# BoardB-FPGA2.net
KiCad netlist of a schematic drawn in Altium Designer
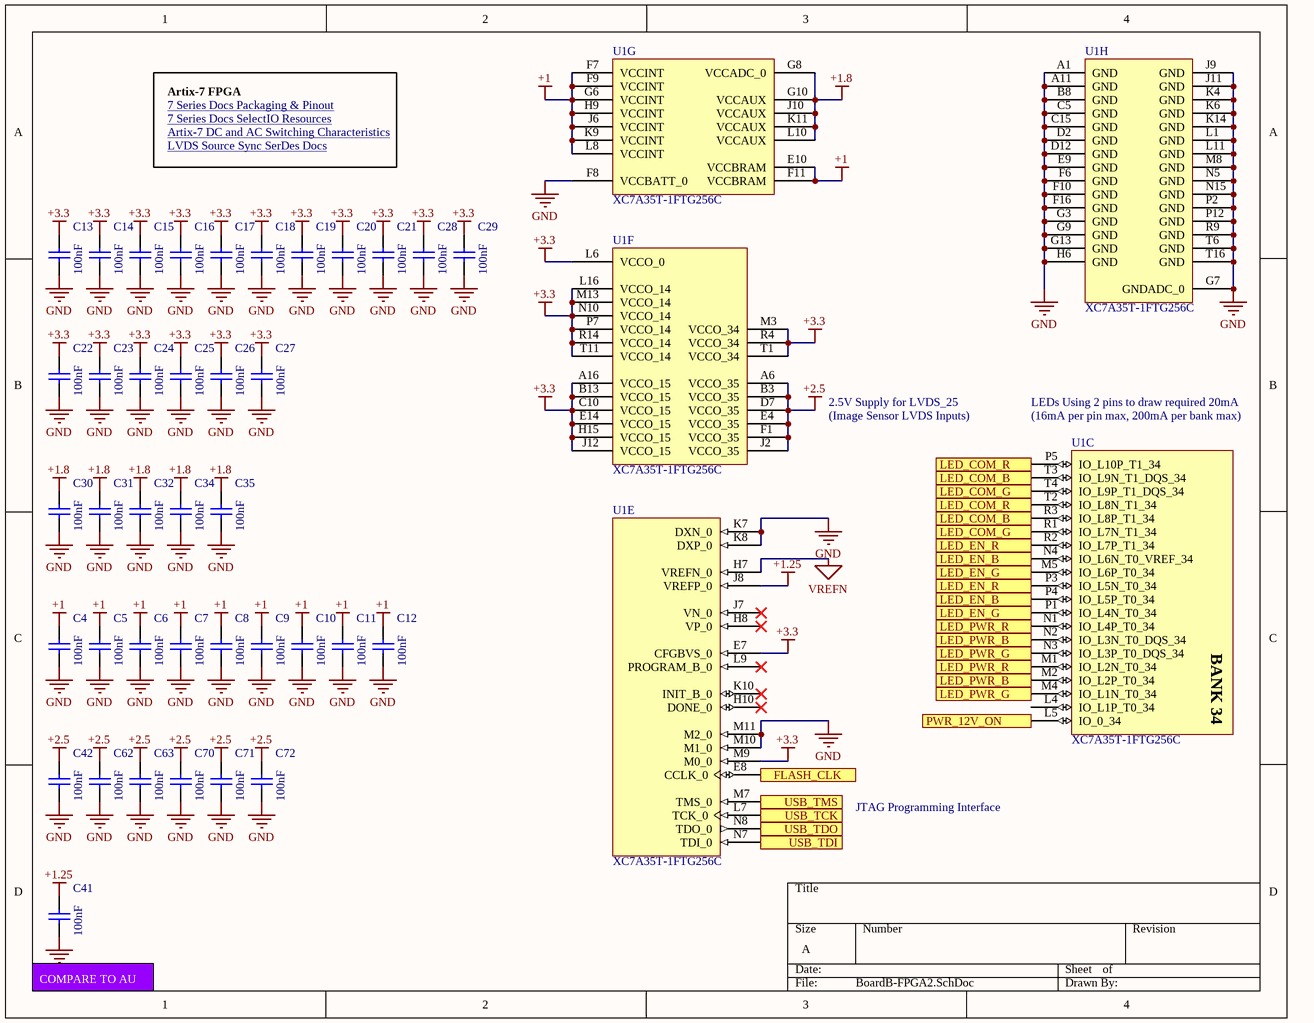
[diagram p0: BoardB-FPGA2.SchDoc]

(export (version "E")
  (design (tool "Eeschema 10.0.6"))
  (components
    (comp (ref "C4")
      (value "100nF")
      (footprint "CAPC0603X33X15ML03T05")
      (fields (field (name "MANUFACTURER") "Samsung") (field (name "PART NUMBER") "CL03A104KQ3NNNC"))
      (libsource (lib "Altium Content Vault") (part "CAP"))
    )
    (comp (ref "C5")
      (value "100nF")
      (footprint "CAPC0603X33X15ML03T05")
      (fields (field (name "MANUFACTURER") "Samsung") (field (name "PART NUMBER") "CL03A104KQ3NNNC"))
      (libsource (lib "Altium Content Vault") (part "CAP"))
    )
    (comp (ref "C6")
      (value "100nF")
      (footprint "CAPC0603X33X15ML03T05")
      (fields (field (name "MANUFACTURER") "Samsung") (field (name "PART NUMBER") "CL03A104KQ3NNNC"))
      (libsource (lib "Altium Content Vault") (part "CAP"))
    )
    (comp (ref "C7")
      (value "100nF")
      (footprint "CAPC0603X33X15ML03T05")
      (fields (field (name "MANUFACTURER") "Samsung") (field (name "PART NUMBER") "CL03A104KQ3NNNC"))
      (libsource (lib "Altium Content Vault") (part "CAP"))
    )
    (comp (ref "C8")
      (value "100nF")
      (footprint "CAPC0603X33X15ML03T05")
      (fields (field (name "MANUFACTURER") "Samsung") (field (name "PART NUMBER") "CL03A104KQ3NNNC"))
      (libsource (lib "Altium Content Vault") (part "CAP"))
    )
    (comp (ref "C9")
      (value "100nF")
      (footprint "CAPC0603X33X15ML03T05")
      (fields (field (name "MANUFACTURER") "Samsung") (field (name "PART NUMBER") "CL03A104KQ3NNNC"))
      (libsource (lib "Altium Content Vault") (part "CAP"))
    )
    (comp (ref "C10")
      (value "100nF")
      (footprint "CAPC0603X33X15ML03T05")
      (fields (field (name "MANUFACTURER") "Samsung") (field (name "PART NUMBER") "CL03A104KQ3NNNC"))
      (libsource (lib "Altium Content Vault") (part "CAP"))
    )
    (comp (ref "C11")
      (value "100nF")
      (footprint "CAPC0603X33X15ML03T05")
      (fields (field (name "MANUFACTURER") "Samsung") (field (name "PART NUMBER") "CL03A104KQ3NNNC"))
      (libsource (lib "Altium Content Vault") (part "CAP"))
    )
    (comp (ref "C12")
      (value "100nF")
      (footprint "CAPC0603X33X15ML03T05")
      (fields (field (name "MANUFACTURER") "Samsung") (field (name "PART NUMBER") "CL03A104KQ3NNNC"))
      (libsource (lib "Altium Content Vault") (part "CAP"))
    )
    (comp (ref "C13")
      (value "100nF")
      (footprint "CAPC0603X33X15ML03T05")
      (fields (field (name "MANUFACTURER") "Samsung") (field (name "PART NUMBER") "CL03A104KQ3NNNC"))
      (libsource (lib "Altium Content Vault") (part "CAP"))
    )
    (comp (ref "C14")
      (value "100nF")
      (footprint "CAPC0603X33X15ML03T05")
      (fields (field (name "MANUFACTURER") "Samsung") (field (name "PART NUMBER") "CL03A104KQ3NNNC"))
      (libsource (lib "Altium Content Vault") (part "CAP"))
    )
    (comp (ref "C15")
      (value "100nF")
      (footprint "CAPC0603X33X15ML03T05")
      (fields (field (name "MANUFACTURER") "Samsung") (field (name "PART NUMBER") "CL03A104KQ3NNNC"))
      (libsource (lib "Altium Content Vault") (part "CAP"))
    )
    (comp (ref "C16")
      (value "100nF")
      (footprint "CAPC0603X33X15ML03T05")
      (fields (field (name "MANUFACTURER") "Samsung") (field (name "PART NUMBER") "CL03A104KQ3NNNC"))
      (libsource (lib "Altium Content Vault") (part "CAP"))
    )
    (comp (ref "C17")
      (value "100nF")
      (footprint "CAPC0603X33X15ML03T05")
      (fields (field (name "MANUFACTURER") "Samsung") (field (name "PART NUMBER") "CL03A104KQ3NNNC"))
      (libsource (lib "Altium Content Vault") (part "CAP"))
    )
    (comp (ref "C18")
      (value "100nF")
      (footprint "CAPC0603X33X15ML03T05")
      (fields (field (name "MANUFACTURER") "Samsung") (field (name "PART NUMBER") "CL03A104KQ3NNNC"))
      (libsource (lib "Altium Content Vault") (part "CAP"))
    )
    (comp (ref "C19")
      (value "100nF")
      (footprint "CAPC0603X33X15ML03T05")
      (fields (field (name "MANUFACTURER") "Samsung") (field (name "PART NUMBER") "CL03A104KQ3NNNC"))
      (libsource (lib "Altium Content Vault") (part "CAP"))
    )
    (comp (ref "C20")
      (value "100nF")
      (footprint "CAPC0603X33X15ML03T05")
      (fields (field (name "MANUFACTURER") "Samsung") (field (name "PART NUMBER") "CL03A104KQ3NNNC"))
      (libsource (lib "Altium Content Vault") (part "CAP"))
    )
    (comp (ref "C21")
      (value "100nF")
      (footprint "CAPC0603X33X15ML03T05")
      (fields (field (name "MANUFACTURER") "Samsung") (field (name "PART NUMBER") "CL03A104KQ3NNNC"))
      (libsource (lib "Altium Content Vault") (part "CAP"))
    )
    (comp (ref "C22")
      (value "100nF")
      (footprint "CAPC0603X33X15ML03T05")
      (fields (field (name "MANUFACTURER") "Samsung") (field (name "PART NUMBER") "CL03A104KQ3NNNC"))
      (libsource (lib "Altium Content Vault") (part "CAP"))
    )
    (comp (ref "C23")
      (value "100nF")
      (footprint "CAPC0603X33X15ML03T05")
      (fields (field (name "MANUFACTURER") "Samsung") (field (name "PART NUMBER") "CL03A104KQ3NNNC"))
      (libsource (lib "Altium Content Vault") (part "CAP"))
    )
    (comp (ref "C24")
      (value "100nF")
      (footprint "CAPC0603X33X15ML03T05")
      (fields (field (name "MANUFACTURER") "Samsung") (field (name "PART NUMBER") "CL03A104KQ3NNNC"))
      (libsource (lib "Altium Content Vault") (part "CAP"))
    )
    (comp (ref "C25")
      (value "100nF")
      (footprint "CAPC0603X33X15ML03T05")
      (fields (field (name "MANUFACTURER") "Samsung") (field (name "PART NUMBER") "CL03A104KQ3NNNC"))
      (libsource (lib "Altium Content Vault") (part "CAP"))
    )
    (comp (ref "C26")
      (value "100nF")
      (footprint "CAPC0603X33X15ML03T05")
      (fields (field (name "MANUFACTURER") "Samsung") (field (name "PART NUMBER") "CL03A104KQ3NNNC"))
      (libsource (lib "Altium Content Vault") (part "CAP"))
    )
    (comp (ref "C27")
      (value "100nF")
      (footprint "CAPC0603X33X15ML03T05")
      (fields (field (name "MANUFACTURER") "Samsung") (field (name "PART NUMBER") "CL03A104KQ3NNNC"))
      (libsource (lib "Altium Content Vault") (part "CAP"))
    )
    (comp (ref "C28")
      (value "100nF")
      (footprint "CAPC0603X33X15ML03T05")
      (fields (field (name "MANUFACTURER") "Samsung") (field (name "PART NUMBER") "CL03A104KQ3NNNC"))
      (libsource (lib "Altium Content Vault") (part "CAP"))
    )
    (comp (ref "C29")
      (value "100nF")
      (footprint "CAPC0603X33X15ML03T05")
      (fields (field (name "MANUFACTURER") "Samsung") (field (name "PART NUMBER") "CL03A104KQ3NNNC"))
      (libsource (lib "Altium Content Vault") (part "CAP"))
    )
    (comp (ref "C30")
      (value "100nF")
      (footprint "CAPC0603X33X15ML03T05")
      (fields (field (name "MANUFACTURER") "Samsung") (field (name "PART NUMBER") "CL03A104KQ3NNNC"))
      (libsource (lib "Altium Content Vault") (part "CAP"))
    )
    (comp (ref "C31")
      (value "100nF")
      (footprint "CAPC0603X33X15ML03T05")
      (fields (field (name "MANUFACTURER") "Samsung") (field (name "PART NUMBER") "CL03A104KQ3NNNC"))
      (libsource (lib "Altium Content Vault") (part "CAP"))
    )
    (comp (ref "C32")
      (value "100nF")
      (footprint "CAPC0603X33X15ML03T05")
      (fields (field (name "MANUFACTURER") "Samsung") (field (name "PART NUMBER") "CL03A104KQ3NNNC"))
      (libsource (lib "Altium Content Vault") (part "CAP"))
    )
    (comp (ref "C34")
      (value "100nF")
      (footprint "CAPC0603X33X15ML03T05")
      (fields (field (name "MANUFACTURER") "Samsung") (field (name "PART NUMBER") "CL03A104KQ3NNNC"))
      (libsource (lib "Altium Content Vault") (part "CAP"))
    )
    (comp (ref "C35")
      (value "100nF")
      (footprint "CAPC0603X33X15ML03T05")
      (fields (field (name "MANUFACTURER") "Samsung") (field (name "PART NUMBER") "CL03A104KQ3NNNC"))
      (libsource (lib "Altium Content Vault") (part "CAP"))
    )
    (comp (ref "C41")
      (value "100nF")
      (footprint "CAPC0603X33X15ML03T05")
      (fields (field (name "MANUFACTURER") "Samsung") (field (name "PART NUMBER") "CL03A104KQ3NNNC"))
      (libsource (lib "Altium Content Vault") (part "CAP"))
    )
    (comp (ref "C42")
      (value "100nF")
      (footprint "CAPC0603X33X15ML03T05")
      (fields (field (name "MANUFACTURER") "Samsung") (field (name "PART NUMBER") "CL03A104KQ3NNNC"))
      (libsource (lib "Altium Content Vault") (part "CAP"))
    )
    (comp (ref "C62")
      (value "100nF")
      (footprint "CAPC0603X33X15ML03T05")
      (fields (field (name "MANUFACTURER") "Samsung") (field (name "PART NUMBER") "CL03A104KQ3NNNC"))
      (libsource (lib "Altium Content Vault") (part "CAP"))
    )
    (comp (ref "C63")
      (value "100nF")
      (footprint "CAPC0603X33X15ML03T05")
      (fields (field (name "MANUFACTURER") "Samsung") (field (name "PART NUMBER") "CL03A104KQ3NNNC"))
      (libsource (lib "Altium Content Vault") (part "CAP"))
    )
    (comp (ref "C70")
      (value "100nF")
      (footprint "CAPC0603X33X15ML03T05")
      (fields (field (name "MANUFACTURER") "Samsung") (field (name "PART NUMBER") "CL03A104KQ3NNNC"))
      (libsource (lib "Altium Content Vault") (part "CAP"))
    )
    (comp (ref "C71")
      (value "100nF")
      (footprint "CAPC0603X33X15ML03T05")
      (fields (field (name "MANUFACTURER") "Samsung") (field (name "PART NUMBER") "CL03A104KQ3NNNC"))
      (libsource (lib "Altium Content Vault") (part "CAP"))
    )
    (comp (ref "C72")
      (value "100nF")
      (footprint "CAPC0603X33X15ML03T05")
      (fields (field (name "MANUFACTURER") "Samsung") (field (name "PART NUMBER") "CL03A104KQ3NNNC"))
      (libsource (lib "Altium Content Vault") (part "CAP"))
    )
    (comp (ref "U1")
      (value "XC7A35T-1FTG256C")
      (footprint "FTG256")
      (description "Artix-7 FPGA, 170 User I/Os, 0 GTP, 256-Ball BGA, Speed Grade 1, Commercial Grade, Pb-Free")
      (fields (field (name "MANUFACTURER") "Xilinx"))
      (libsource (lib "") (part "XLNX-XC7A35T-FTG256_1"))
    )
  )
  (nets
    (net (code "1") (name "+1") (class "Default")
      (node (ref "C10") (pin "2") (pinfunction "2_2") (pintype "passive"))
      (node (ref "C11") (pin "2") (pinfunction "2_2") (pintype "passive"))
      (node (ref "C12") (pin "2") (pinfunction "2_2") (pintype "passive"))
      (node (ref "C4") (pin "2") (pinfunction "2_2") (pintype "passive"))
      (node (ref "C5") (pin "2") (pinfunction "2_2") (pintype "passive"))
      (node (ref "C6") (pin "2") (pinfunction "2_2") (pintype "passive"))
      (node (ref "C7") (pin "2") (pinfunction "2_2") (pintype "passive"))
      (node (ref "C8") (pin "2") (pinfunction "2_2") (pintype "passive"))
      (node (ref "C9") (pin "2") (pinfunction "2_2") (pintype "passive"))
      (node (ref "U1") (pin "E10") (pinfunction "VCCBRAM_E10") (pintype "power_in"))
      (node (ref "U1") (pin "F11") (pinfunction "VCCBRAM_F11") (pintype "power_in"))
      (node (ref "U1") (pin "F7") (pinfunction "VCCINT_F7") (pintype "power_in"))
      (node (ref "U1") (pin "F9") (pinfunction "VCCINT_F9") (pintype "power_in"))
      (node (ref "U1") (pin "G6") (pinfunction "VCCINT_G6") (pintype "power_in"))
      (node (ref "U1") (pin "H9") (pinfunction "VCCINT_H9") (pintype "power_in"))
      (node (ref "U1") (pin "J6") (pinfunction "VCCINT_J6") (pintype "power_in"))
      (node (ref "U1") (pin "K9") (pinfunction "VCCINT_K9") (pintype "power_in"))
      (node (ref "U1") (pin "L8") (pinfunction "VCCINT_L8") (pintype "power_in"))
    )
    (net (code "2") (name "+1.8") (class "Default")
      (node (ref "C30") (pin "2") (pinfunction "2_2") (pintype "passive"))
      (node (ref "C31") (pin "2") (pinfunction "2_2") (pintype "passive"))
      (node (ref "C32") (pin "2") (pinfunction "2_2") (pintype "passive"))
      (node (ref "C34") (pin "2") (pinfunction "2_2") (pintype "passive"))
      (node (ref "C35") (pin "2") (pinfunction "2_2") (pintype "passive"))
      (node (ref "U1") (pin "G10") (pinfunction "VCCAUX_G10") (pintype "power_in"))
      (node (ref "U1") (pin "G8") (pinfunction "VCCADC_0_G8") (pintype "power_in"))
      (node (ref "U1") (pin "J10") (pinfunction "VCCAUX_J10") (pintype "power_in"))
      (node (ref "U1") (pin "K11") (pinfunction "VCCAUX_K11") (pintype "power_in"))
      (node (ref "U1") (pin "L10") (pinfunction "VCCAUX_L10") (pintype "power_in"))
    )
    (net (code "3") (name "+1.25") (class "Default")
      (node (ref "C41") (pin "2") (pinfunction "2_2") (pintype "passive"))
      (node (ref "U1") (pin "J8") (pinfunction "VREFP_0_J8") (pintype "input"))
    )
    (net (code "4") (name "+2.5") (class "Default")
      (node (ref "C42") (pin "2") (pinfunction "2_2") (pintype "passive"))
      (node (ref "C62") (pin "2") (pinfunction "2_2") (pintype "passive"))
      (node (ref "C63") (pin "2") (pinfunction "2_2") (pintype "passive"))
      (node (ref "C70") (pin "2") (pinfunction "2_2") (pintype "passive"))
      (node (ref "C71") (pin "2") (pinfunction "2_2") (pintype "passive"))
      (node (ref "C72") (pin "2") (pinfunction "2_2") (pintype "passive"))
      (node (ref "U1") (pin "A6") (pinfunction "VCCO_35_A6") (pintype "power_in"))
      (node (ref "U1") (pin "B3") (pinfunction "VCCO_35_B3") (pintype "power_in"))
      (node (ref "U1") (pin "D7") (pinfunction "VCCO_35_D7") (pintype "power_in"))
      (node (ref "U1") (pin "E4") (pinfunction "VCCO_35_E4") (pintype "power_in"))
      (node (ref "U1") (pin "F1") (pinfunction "VCCO_35_F1") (pintype "power_in"))
      (node (ref "U1") (pin "J2") (pinfunction "VCCO_35_J2") (pintype "power_in"))
    )
    (net (code "5") (name "+3.3") (class "Default")
      (node (ref "C13") (pin "2") (pinfunction "2_2") (pintype "passive"))
      (node (ref "C14") (pin "2") (pinfunction "2_2") (pintype "passive"))
      (node (ref "C15") (pin "2") (pinfunction "2_2") (pintype "passive"))
      (node (ref "C16") (pin "2") (pinfunction "2_2") (pintype "passive"))
      (node (ref "C17") (pin "2") (pinfunction "2_2") (pintype "passive"))
      (node (ref "C18") (pin "2") (pinfunction "2_2") (pintype "passive"))
      (node (ref "C19") (pin "2") (pinfunction "2_2") (pintype "passive"))
      (node (ref "C20") (pin "2") (pinfunction "2_2") (pintype "passive"))
      (node (ref "C21") (pin "2") (pinfunction "2_2") (pintype "passive"))
      (node (ref "C22") (pin "2") (pinfunction "2_2") (pintype "passive"))
      (node (ref "C23") (pin "2") (pinfunction "2_2") (pintype "passive"))
      (node (ref "C24") (pin "2") (pinfunction "2_2") (pintype "passive"))
      (node (ref "C25") (pin "2") (pinfunction "2_2") (pintype "passive"))
      (node (ref "C26") (pin "2") (pinfunction "2_2") (pintype "passive"))
      (node (ref "C27") (pin "2") (pinfunction "2_2") (pintype "passive"))
      (node (ref "C28") (pin "2") (pinfunction "2_2") (pintype "passive"))
      (node (ref "C29") (pin "2") (pinfunction "2_2") (pintype "passive"))
      (node (ref "U1") (pin "A16") (pinfunction "VCCO_15_A16") (pintype "power_in"))
      (node (ref "U1") (pin "B13") (pinfunction "VCCO_15_B13") (pintype "power_in"))
      (node (ref "U1") (pin "C10") (pinfunction "VCCO_15_C10") (pintype "power_in"))
      (node (ref "U1") (pin "E14") (pinfunction "VCCO_15_E14") (pintype "power_in"))
      (node (ref "U1") (pin "E7") (pinfunction "CFGBVS_0_E7") (pintype "input"))
      (node (ref "U1") (pin "H15") (pinfunction "VCCO_15_H15") (pintype "power_in"))
      (node (ref "U1") (pin "J12") (pinfunction "VCCO_15_J12") (pintype "power_in"))
      (node (ref "U1") (pin "L16") (pinfunction "VCCO_14_L16") (pintype "power_in"))
      (node (ref "U1") (pin "L6") (pinfunction "VCCO_0_L6") (pintype "power_in"))
      (node (ref "U1") (pin "M13") (pinfunction "VCCO_14_M13") (pintype "power_in"))
      (node (ref "U1") (pin "M3") (pinfunction "VCCO_34_M3") (pintype "power_in"))
      (node (ref "U1") (pin "M9") (pinfunction "M0_0_M9") (pintype "input"))
      (node (ref "U1") (pin "N10") (pinfunction "VCCO_14_N10") (pintype "power_in"))
      (node (ref "U1") (pin "P7") (pinfunction "VCCO_14_P7") (pintype "power_in"))
      (node (ref "U1") (pin "R14") (pinfunction "VCCO_14_R14") (pintype "power_in"))
      (node (ref "U1") (pin "R4") (pinfunction "VCCO_34_R4") (pintype "power_in"))
      (node (ref "U1") (pin "T1") (pinfunction "VCCO_34_T1") (pintype "power_in"))
      (node (ref "U1") (pin "T11") (pinfunction "VCCO_14_T11") (pintype "power_in"))
    )
    (net (code "6") (name "/FLASH_CLK") (class "Default")
      (node (ref "U1") (pin "E8") (pinfunction "CCLK_0_E8") (pintype "bidirectional"))
    )
    (net (code "7") (name "/LED_COM_B") (class "Default")
      (node (ref "U1") (pin "R3") (pinfunction "IO_L8P_T1_34_R3") (pintype "bidirectional"))
      (node (ref "U1") (pin "T3") (pinfunction "IO_L9N_T1_DQS_34_T3") (pintype "bidirectional"))
    )
    (net (code "8") (name "/LED_COM_G") (class "Default")
      (node (ref "U1") (pin "R1") (pinfunction "IO_L7N_T1_34_R1") (pintype "bidirectional"))
      (node (ref "U1") (pin "T4") (pinfunction "IO_L9P_T1_DQS_34_T4") (pintype "bidirectional"))
    )
    (net (code "9") (name "/LED_COM_R") (class "Default")
      (node (ref "U1") (pin "P5") (pinfunction "IO_L10P_T1_34_P5") (pintype "bidirectional"))
      (node (ref "U1") (pin "T2") (pinfunction "IO_L8N_T1_34_T2") (pintype "bidirectional"))
    )
    (net (code "10") (name "/LED_EN_B") (class "Default")
      (node (ref "U1") (pin "N4") (pinfunction "IO_L6N_T0_VREF_34_N4") (pintype "bidirectional"))
      (node (ref "U1") (pin "P4") (pinfunction "IO_L5P_T0_34_P4") (pintype "bidirectional"))
    )
    (net (code "11") (name "/LED_EN_G") (class "Default")
      (node (ref "U1") (pin "M5") (pinfunction "IO_L6P_T0_34_M5") (pintype "bidirectional"))
      (node (ref "U1") (pin "P1") (pinfunction "IO_L4N_T0_34_P1") (pintype "bidirectional"))
    )
    (net (code "12") (name "/LED_EN_R") (class "Default")
      (node (ref "U1") (pin "P3") (pinfunction "IO_L5N_T0_34_P3") (pintype "bidirectional"))
      (node (ref "U1") (pin "R2") (pinfunction "IO_L7P_T1_34_R2") (pintype "bidirectional"))
    )
    (net (code "13") (name "/LED_PWR_B") (class "Default")
      (node (ref "U1") (pin "M2") (pinfunction "IO_L2P_T0_34_M2") (pintype "bidirectional"))
      (node (ref "U1") (pin "N2") (pinfunction "IO_L3N_T0_DQS_34_N2") (pintype "bidirectional"))
    )
    (net (code "14") (name "/LED_PWR_G") (class "Default")
      (node (ref "U1") (pin "M4") (pinfunction "IO_L1N_T0_34_M4") (pintype "bidirectional"))
      (node (ref "U1") (pin "N3") (pinfunction "IO_L3P_T0_DQS_34_N3") (pintype "bidirectional"))
    )
    (net (code "15") (name "/LED_PWR_R") (class "Default")
      (node (ref "U1") (pin "M1") (pinfunction "IO_L2N_T0_34_M1") (pintype "bidirectional"))
      (node (ref "U1") (pin "N1") (pinfunction "IO_L4P_T0_34_N1") (pintype "bidirectional"))
    )
    (net (code "16") (name "/PWR_12V_ON") (class "Default")
      (node (ref "U1") (pin "L5") (pinfunction "IO_0_34_L5") (pintype "bidirectional"))
    )
    (net (code "17") (name "/USB_TCK") (class "Default")
      (node (ref "U1") (pin "L7") (pinfunction "TCK_0_L7") (pintype "input"))
    )
    (net (code "18") (name "/USB_TDI") (class "Default")
      (node (ref "U1") (pin "N7") (pinfunction "TDI_0_N7") (pintype "input"))
    )
    (net (code "19") (name "/USB_TDO") (class "Default")
      (node (ref "U1") (pin "N8") (pinfunction "TDO_0_N8") (pintype "output"))
    )
    (net (code "20") (name "/USB_TMS") (class "Default")
      (node (ref "U1") (pin "M7") (pinfunction "TMS_0_M7") (pintype "input"))
    )
    (net (code "21") (name "GND") (class "Default")
      (node (ref "C10") (pin "1") (pinfunction "1_1") (pintype "passive"))
      (node (ref "C11") (pin "1") (pinfunction "1_1") (pintype "passive"))
      (node (ref "C12") (pin "1") (pinfunction "1_1") (pintype "passive"))
      (node (ref "C13") (pin "1") (pinfunction "1_1") (pintype "passive"))
      (node (ref "C14") (pin "1") (pinfunction "1_1") (pintype "passive"))
      (node (ref "C15") (pin "1") (pinfunction "1_1") (pintype "passive"))
      (node (ref "C16") (pin "1") (pinfunction "1_1") (pintype "passive"))
      (node (ref "C17") (pin "1") (pinfunction "1_1") (pintype "passive"))
      (node (ref "C18") (pin "1") (pinfunction "1_1") (pintype "passive"))
      (node (ref "C19") (pin "1") (pinfunction "1_1") (pintype "passive"))
      (node (ref "C20") (pin "1") (pinfunction "1_1") (pintype "passive"))
      (node (ref "C21") (pin "1") (pinfunction "1_1") (pintype "passive"))
      (node (ref "C22") (pin "1") (pinfunction "1_1") (pintype "passive"))
      (node (ref "C23") (pin "1") (pinfunction "1_1") (pintype "passive"))
      (node (ref "C24") (pin "1") (pinfunction "1_1") (pintype "passive"))
      (node (ref "C25") (pin "1") (pinfunction "1_1") (pintype "passive"))
      (node (ref "C26") (pin "1") (pinfunction "1_1") (pintype "passive"))
      (node (ref "C27") (pin "1") (pinfunction "1_1") (pintype "passive"))
      (node (ref "C28") (pin "1") (pinfunction "1_1") (pintype "passive"))
      (node (ref "C29") (pin "1") (pinfunction "1_1") (pintype "passive"))
      (node (ref "C30") (pin "1") (pinfunction "1_1") (pintype "passive"))
      (node (ref "C31") (pin "1") (pinfunction "1_1") (pintype "passive"))
      (node (ref "C32") (pin "1") (pinfunction "1_1") (pintype "passive"))
      (node (ref "C34") (pin "1") (pinfunction "1_1") (pintype "passive"))
      (node (ref "C35") (pin "1") (pinfunction "1_1") (pintype "passive"))
      (node (ref "C4") (pin "1") (pinfunction "1_1") (pintype "passive"))
      (node (ref "C41") (pin "1") (pinfunction "1_1") (pintype "passive"))
      (node (ref "C42") (pin "1") (pinfunction "1_1") (pintype "passive"))
      (node (ref "C5") (pin "1") (pinfunction "1_1") (pintype "passive"))
      (node (ref "C6") (pin "1") (pinfunction "1_1") (pintype "passive"))
      (node (ref "C62") (pin "1") (pinfunction "1_1") (pintype "passive"))
      (node (ref "C63") (pin "1") (pinfunction "1_1") (pintype "passive"))
      (node (ref "C7") (pin "1") (pinfunction "1_1") (pintype "passive"))
      (node (ref "C70") (pin "1") (pinfunction "1_1") (pintype "passive"))
      (node (ref "C71") (pin "1") (pinfunction "1_1") (pintype "passive"))
      (node (ref "C72") (pin "1") (pinfunction "1_1") (pintype "passive"))
      (node (ref "C8") (pin "1") (pinfunction "1_1") (pintype "passive"))
      (node (ref "C9") (pin "1") (pinfunction "1_1") (pintype "passive"))
      (node (ref "U1") (pin "A1") (pinfunction "GND_A1") (pintype "power_in"))
      (node (ref "U1") (pin "A11") (pinfunction "GND_A11") (pintype "power_in"))
      (node (ref "U1") (pin "B8") (pinfunction "GND_B8") (pintype "power_in"))
      (node (ref "U1") (pin "C15") (pinfunction "GND_C15") (pintype "power_in"))
      (node (ref "U1") (pin "C5") (pinfunction "GND_C5") (pintype "power_in"))
      (node (ref "U1") (pin "D12") (pinfunction "GND_D12") (pintype "power_in"))
      (node (ref "U1") (pin "D2") (pinfunction "GND_D2") (pintype "power_in"))
      (node (ref "U1") (pin "E9") (pinfunction "GND_E9") (pintype "power_in"))
      (node (ref "U1") (pin "F10") (pinfunction "GND_F10") (pintype "power_in"))
      (node (ref "U1") (pin "F16") (pinfunction "GND_F16") (pintype "power_in"))
      (node (ref "U1") (pin "F6") (pinfunction "GND_F6") (pintype "power_in"))
      (node (ref "U1") (pin "F8") (pinfunction "VCCBATT_0_F8") (pintype "power_in"))
      (node (ref "U1") (pin "G13") (pinfunction "GND_G13") (pintype "power_in"))
      (node (ref "U1") (pin "G3") (pinfunction "GND_G3") (pintype "power_in"))
      (node (ref "U1") (pin "G7") (pinfunction "GNDADC_0_G7") (pintype "power_in"))
      (node (ref "U1") (pin "G9") (pinfunction "GND_G9") (pintype "power_in"))
      (node (ref "U1") (pin "H6") (pinfunction "GND_H6") (pintype "power_in"))
      (node (ref "U1") (pin "J11") (pinfunction "GND_J11") (pintype "power_in"))
      (node (ref "U1") (pin "J9") (pinfunction "GND_J9") (pintype "power_in"))
      (node (ref "U1") (pin "K14") (pinfunction "GND_K14") (pintype "power_in"))
      (node (ref "U1") (pin "K4") (pinfunction "GND_K4") (pintype "power_in"))
      (node (ref "U1") (pin "K6") (pinfunction "GND_K6") (pintype "power_in"))
      (node (ref "U1") (pin "K7") (pinfunction "DXN_0_K7") (pintype "input"))
      (node (ref "U1") (pin "K8") (pinfunction "DXP_0_K8") (pintype "input"))
      (node (ref "U1") (pin "L1") (pinfunction "GND_L1") (pintype "power_in"))
      (node (ref "U1") (pin "L11") (pinfunction "GND_L11") (pintype "power_in"))
      (node (ref "U1") (pin "M10") (pinfunction "M1_0_M10") (pintype "input"))
      (node (ref "U1") (pin "M11") (pinfunction "M2_0_M11") (pintype "input"))
      (node (ref "U1") (pin "M8") (pinfunction "GND_M8") (pintype "power_in"))
      (node (ref "U1") (pin "N15") (pinfunction "GND_N15") (pintype "power_in"))
      (node (ref "U1") (pin "N5") (pinfunction "GND_N5") (pintype "power_in"))
      (node (ref "U1") (pin "P12") (pinfunction "GND_P12") (pintype "power_in"))
      (node (ref "U1") (pin "P2") (pinfunction "GND_P2") (pintype "power_in"))
      (node (ref "U1") (pin "R9") (pinfunction "GND_R9") (pintype "power_in"))
      (node (ref "U1") (pin "T16") (pinfunction "GND_T16") (pintype "power_in"))
      (node (ref "U1") (pin "T6") (pinfunction "GND_T6") (pintype "power_in"))
    )
    (net (code "22") (name "VREFN") (class "Default")
      (node (ref "U1") (pin "H7") (pinfunction "VREFN_0_H7") (pintype "input"))
    )
    (net (code "23") (name "unconnected-(U1C-IO_L1P_T0_34-PadL4)") (class "Default")
      (node (ref "U1") (pin "L4") (pinfunction "IO_L1P_T0_34_L4") (pintype "bidirectional"))
    )
    (net (code "24") (name "unconnected-(U1E-DONE_0-PadH10)") (class "Default")
      (node (ref "U1") (pin "H10") (pinfunction "DONE_0_H10") (pintype "bidirectional+no_connect"))
    )
    (net (code "25") (name "unconnected-(U1E-INIT_B_0-PadK10)") (class "Default")
      (node (ref "U1") (pin "K10") (pinfunction "INIT_B_0_K10") (pintype "bidirectional+no_connect"))
    )
    (net (code "26") (name "unconnected-(U1E-PROGRAM_B_0-PadL9)") (class "Default")
      (node (ref "U1") (pin "L9") (pinfunction "PROGRAM_B_0_L9") (pintype "input+no_connect"))
    )
    (net (code "27") (name "unconnected-(U1E-VN_0-PadJ7)") (class "Default")
      (node (ref "U1") (pin "J7") (pinfunction "VN_0_J7") (pintype "input+no_connect"))
    )
    (net (code "28") (name "unconnected-(U1E-VP_0-PadH8)") (class "Default")
      (node (ref "U1") (pin "H8") (pinfunction "VP_0_H8") (pintype "input+no_connect"))
    )
  )
)
